# WiringDiagram.net
KiCad netlist of a schematic drawn in EAGLE
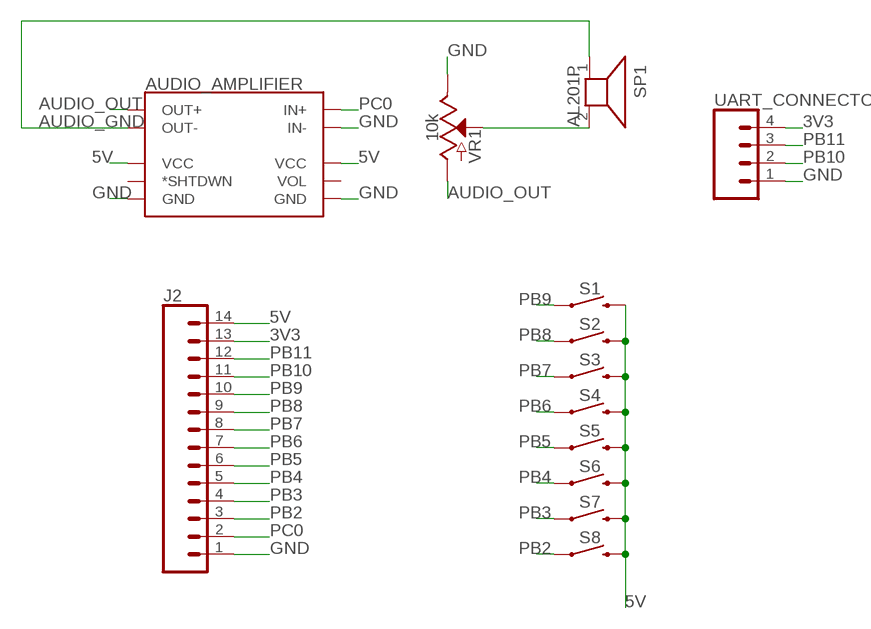
[diagram p0: schematic, sheet 1]

(export (version "E")
  (design (tool "Eeschema 10.0.6"))
  (components
    (comp (ref "AUDIO_AMPLIFIER")
      (value "SPARKFUN_AUDIO-AMP-MONODIP")
      (footprint "eagle-import:AUDIO-AMP-MONO")
      (libsource (lib "eagle-import") (part "SPARKFUN_AUDIO-AMP-MONODIP"))
    )
    (comp (ref "J2")
      (value "CONN_14")
      (footprint "eagle-import:1X14")
      (libsource (lib "eagle-import") (part "CONN_14"))
    )
    (comp (ref "S1")
      (value "MOMENTARY-SWITCH-SPST-PTH-6.0MM")
      (footprint "eagle-import:TACTILE_SWITCH_PTH_6.0MM")
      (libsource (lib "eagle-import") (part "MOMENTARY-SWITCH-SPST-PTH-6.0MM"))
    )
    (comp (ref "S2")
      (value "MOMENTARY-SWITCH-SPST-PTH-6.0MM")
      (footprint "eagle-import:TACTILE_SWITCH_PTH_6.0MM")
      (libsource (lib "eagle-import") (part "MOMENTARY-SWITCH-SPST-PTH-6.0MM"))
    )
    (comp (ref "S3")
      (value "MOMENTARY-SWITCH-SPST-PTH-6.0MM")
      (footprint "eagle-import:TACTILE_SWITCH_PTH_6.0MM")
      (libsource (lib "eagle-import") (part "MOMENTARY-SWITCH-SPST-PTH-6.0MM"))
    )
    (comp (ref "S4")
      (value "MOMENTARY-SWITCH-SPST-PTH-6.0MM")
      (footprint "eagle-import:TACTILE_SWITCH_PTH_6.0MM")
      (libsource (lib "eagle-import") (part "MOMENTARY-SWITCH-SPST-PTH-6.0MM"))
    )
    (comp (ref "S5")
      (value "MOMENTARY-SWITCH-SPST-PTH-6.0MM")
      (footprint "eagle-import:TACTILE_SWITCH_PTH_6.0MM")
      (libsource (lib "eagle-import") (part "MOMENTARY-SWITCH-SPST-PTH-6.0MM"))
    )
    (comp (ref "S6")
      (value "MOMENTARY-SWITCH-SPST-PTH-6.0MM")
      (footprint "eagle-import:TACTILE_SWITCH_PTH_6.0MM")
      (libsource (lib "eagle-import") (part "MOMENTARY-SWITCH-SPST-PTH-6.0MM"))
    )
    (comp (ref "S7")
      (value "MOMENTARY-SWITCH-SPST-PTH-6.0MM")
      (footprint "eagle-import:TACTILE_SWITCH_PTH_6.0MM")
      (libsource (lib "eagle-import") (part "MOMENTARY-SWITCH-SPST-PTH-6.0MM"))
    )
    (comp (ref "S8")
      (value "MOMENTARY-SWITCH-SPST-PTH-6.0MM")
      (footprint "eagle-import:TACTILE_SWITCH_PTH_6.0MM")
      (libsource (lib "eagle-import") (part "MOMENTARY-SWITCH-SPST-PTH-6.0MM"))
    )
    (comp (ref "SP1")
      (value "AL201P")
      (footprint "eagle-import:AL201P")
      (libsource (lib "eagle-import") (part "AL201P"))
    )
    (comp (ref "UART_CONNECTOR")
      (value "CONN_04")
      (footprint "eagle-import:1X04")
      (libsource (lib "eagle-import") (part "CONN_04"))
    )
    (comp (ref "VR1")
      (value "10k")
      (footprint "eagle-import:POT-PTH-ALPS")
      (libsource (lib "eagle-import") (part "POTENTIOMETER-PTH-9MM-1/20W-20%"))
    )
  )
  (nets
    (net (code "1") (name "/3V3") (class "Default")
      (node (ref "J2") (pin "13") (pinfunction "13_13") (pintype "passive"))
      (node (ref "UART_CONNECTOR") (pin "4") (pinfunction "4_4") (pintype "passive"))
    )
    (net (code "2") (name "/5V") (class "Default")
      (node (ref "AUDIO_AMPLIFIER") (pin "PWR+") (pinfunction "VCC_PWR+") (pintype "bidirectional"))
      (node (ref "AUDIO_AMPLIFIER") (pin "VOL+") (pinfunction "VCC_VOL+") (pintype "bidirectional"))
      (node (ref "J2") (pin "14") (pinfunction "14_14") (pintype "passive"))
      (node (ref "S1") (pin "3") (pinfunction "2_3") (pintype "passive"))
      (node (ref "S2") (pin "3") (pinfunction "2_3") (pintype "passive"))
      (node (ref "S3") (pin "3") (pinfunction "2_3") (pintype "passive"))
      (node (ref "S4") (pin "3") (pinfunction "2_3") (pintype "passive"))
      (node (ref "S5") (pin "3") (pinfunction "2_3") (pintype "passive"))
      (node (ref "S6") (pin "3") (pinfunction "2_3") (pintype "passive"))
      (node (ref "S7") (pin "3") (pinfunction "2_3") (pintype "passive"))
      (node (ref "S8") (pin "3") (pinfunction "2_3") (pintype "passive"))
    )
    (net (code "3") (name "/AUDIO_GND") (class "Default")
      (node (ref "AUDIO_AMPLIFIER") (pin "OUT-") (pinfunction "OUT-_OUT-") (pintype "bidirectional"))
      (node (ref "SP1") (pin "1") (pinfunction "1_1") (pintype "passive"))
    )
    (net (code "4") (name "/AUDIO_OUT") (class "Default")
      (node (ref "AUDIO_AMPLIFIER") (pin "OUT+") (pinfunction "OUT+_OUT+") (pintype "bidirectional"))
      (node (ref "VR1") (pin "P$3") (pinfunction "A_P$3") (pintype "passive"))
    )
    (net (code "5") (name "/GND") (class "Default")
      (node (ref "AUDIO_AMPLIFIER") (pin "IN-") (pinfunction "IN-_IN-") (pintype "bidirectional"))
      (node (ref "AUDIO_AMPLIFIER") (pin "PWR-") (pinfunction "GND_PWR-") (pintype "bidirectional"))
      (node (ref "AUDIO_AMPLIFIER") (pin "VOL-") (pinfunction "GND_VOL-") (pintype "bidirectional"))
      (node (ref "J2") (pin "1") (pinfunction "1_1") (pintype "passive"))
      (node (ref "UART_CONNECTOR") (pin "1") (pinfunction "1_1") (pintype "passive"))
      (node (ref "VR1") (pin "P$1") (pinfunction "E_P$1") (pintype "passive"))
    )
    (net (code "6") (name "/PB2") (class "Default")
      (node (ref "J2") (pin "3") (pinfunction "3_3") (pintype "passive"))
      (node (ref "S8") (pin "1") (pinfunction "1_1") (pintype "passive"))
    )
    (net (code "7") (name "/PB3") (class "Default")
      (node (ref "J2") (pin "4") (pinfunction "4_4") (pintype "passive"))
      (node (ref "S7") (pin "1") (pinfunction "1_1") (pintype "passive"))
    )
    (net (code "8") (name "/PB4") (class "Default")
      (node (ref "J2") (pin "5") (pinfunction "5_5") (pintype "passive"))
      (node (ref "S6") (pin "1") (pinfunction "1_1") (pintype "passive"))
    )
    (net (code "9") (name "/PB5") (class "Default")
      (node (ref "J2") (pin "6") (pinfunction "6_6") (pintype "passive"))
      (node (ref "S5") (pin "1") (pinfunction "1_1") (pintype "passive"))
    )
    (net (code "10") (name "/PB6") (class "Default")
      (node (ref "J2") (pin "7") (pinfunction "7_7") (pintype "passive"))
      (node (ref "S4") (pin "1") (pinfunction "1_1") (pintype "passive"))
    )
    (net (code "11") (name "/PB7") (class "Default")
      (node (ref "J2") (pin "8") (pinfunction "8_8") (pintype "passive"))
      (node (ref "S3") (pin "1") (pinfunction "1_1") (pintype "passive"))
    )
    (net (code "12") (name "/PB8") (class "Default")
      (node (ref "J2") (pin "9") (pinfunction "9_9") (pintype "passive"))
      (node (ref "S2") (pin "1") (pinfunction "1_1") (pintype "passive"))
    )
    (net (code "13") (name "/PB9") (class "Default")
      (node (ref "J2") (pin "10") (pinfunction "10_10") (pintype "passive"))
      (node (ref "S1") (pin "1") (pinfunction "1_1") (pintype "passive"))
    )
    (net (code "14") (name "/PB10") (class "Default")
      (node (ref "J2") (pin "11") (pinfunction "11_11") (pintype "passive"))
      (node (ref "UART_CONNECTOR") (pin "2") (pinfunction "2_2") (pintype "passive"))
    )
    (net (code "15") (name "/PB11") (class "Default")
      (node (ref "J2") (pin "12") (pinfunction "12_12") (pintype "passive"))
      (node (ref "UART_CONNECTOR") (pin "3") (pinfunction "3_3") (pintype "passive"))
    )
    (net (code "16") (name "/PC0") (class "Default")
      (node (ref "AUDIO_AMPLIFIER") (pin "IN+") (pinfunction "IN+_IN+") (pintype "bidirectional"))
      (node (ref "J2") (pin "2") (pinfunction "2_2") (pintype "passive"))
    )
    (net (code "17") (name "Net-(VR1-S)") (class "Default")
      (node (ref "SP1") (pin "2") (pinfunction "2_2") (pintype "passive"))
      (node (ref "VR1") (pin "P$2") (pinfunction "S_P$2") (pintype "passive"))
    )
    (net (code "18") (name "unconnected-(AUDIO_AMPLIFIER-*SHTDWN-PadS)") (class "Default")
      (node (ref "AUDIO_AMPLIFIER") (pin "S") (pinfunction "*SHTDWN_S") (pintype "bidirectional"))
    )
    (net (code "19") (name "unconnected-(AUDIO_AMPLIFIER-PadVOL)") (class "Default")
      (node (ref "AUDIO_AMPLIFIER") (pin "VOL") (pinfunction "VOL_VOL") (pintype "bidirectional"))
    )
  )
)
